# smartmeterif.net
KiCad netlist of a schematic drawn in EAGLE
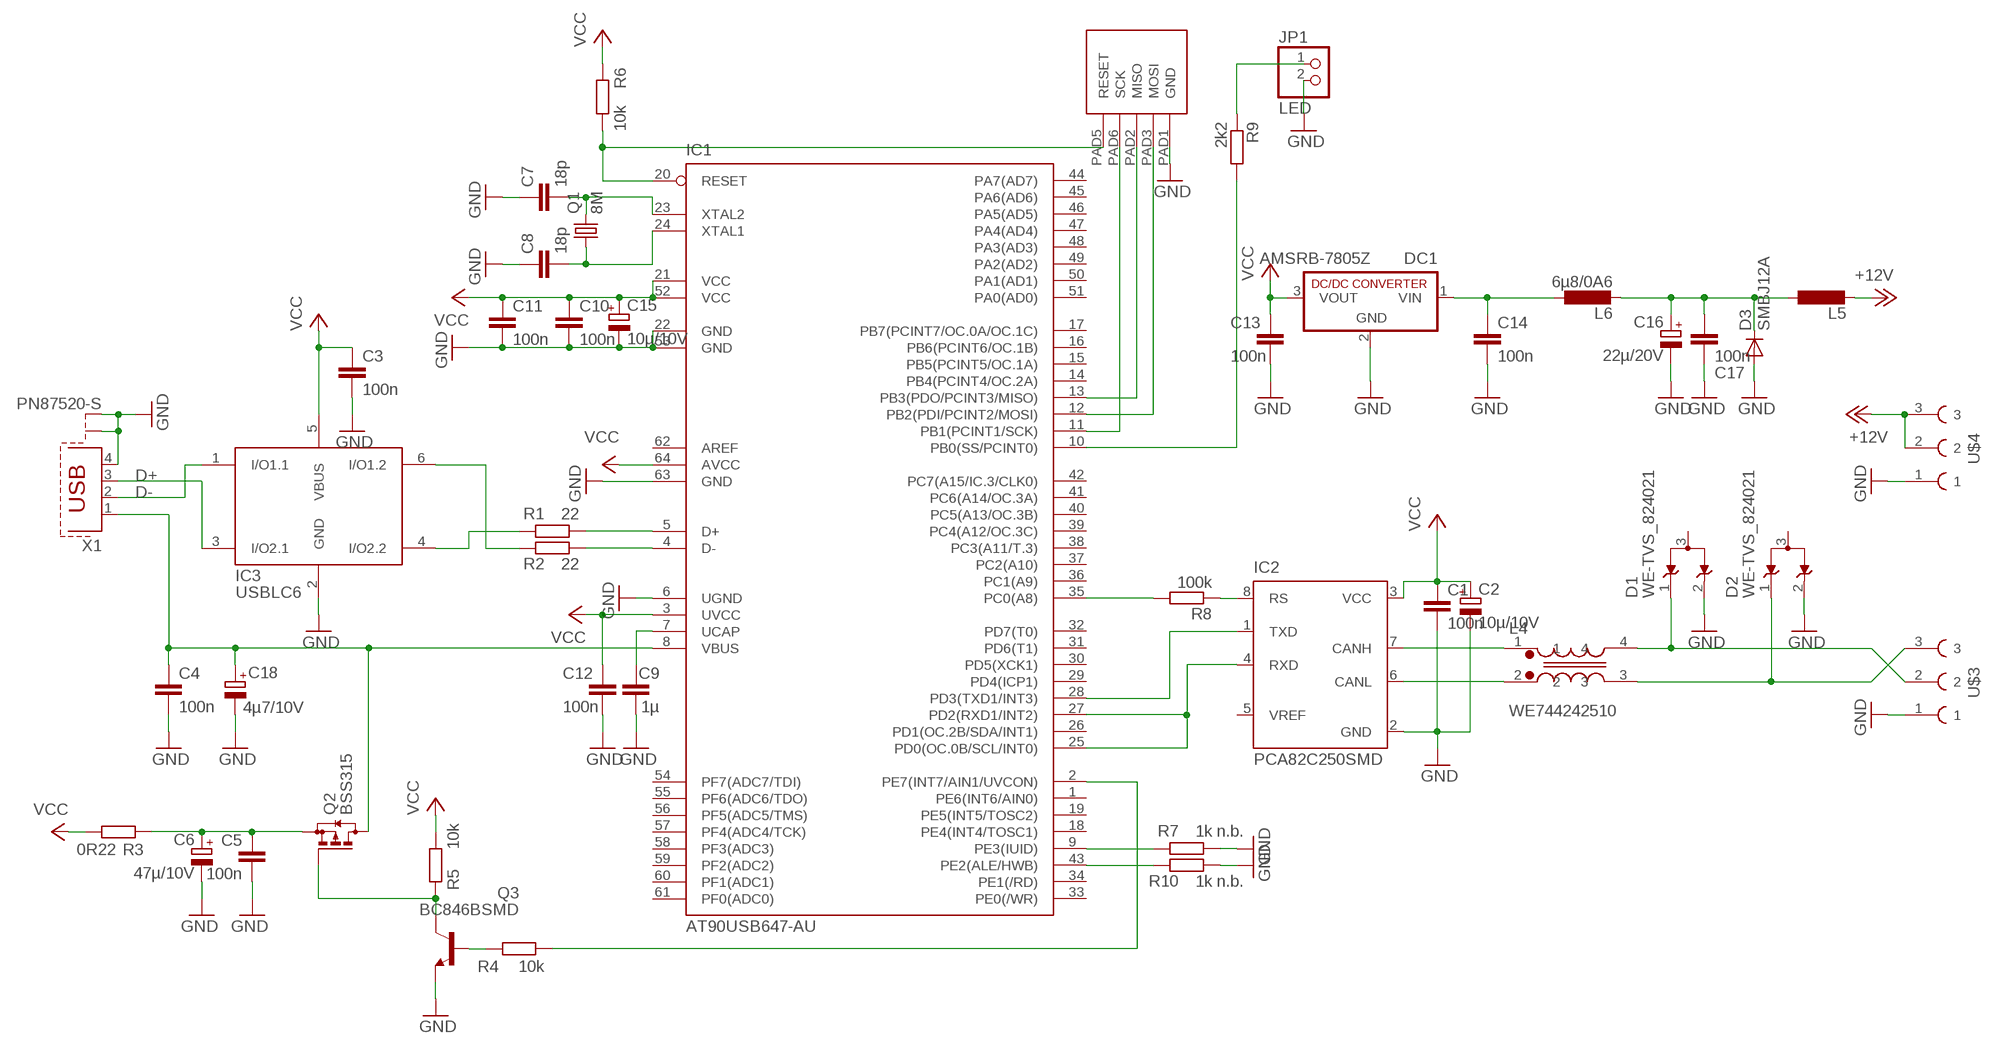
[diagram p0: schematic, sheet 1]

(export (version "E")
  (design (tool "Eeschema 10.0.6"))
  (components
    (comp (ref "C1")
      (value "100n")
      (footprint "eagle-import:C0603")
      (libsource (lib "eagle-import") (part "resistor_C-EUC0603"))
    )
    (comp (ref "C2")
      (value "10µ/10V")
      (footprint "eagle-import:A_3216-18W")
      (libsource (lib "eagle-import") (part "CPOL-EUA/3216-18W"))
    )
    (comp (ref "C3")
      (value "100n")
      (footprint "eagle-import:C0603")
      (libsource (lib "eagle-import") (part "resistor_C-EUC0603"))
    )
    (comp (ref "C4")
      (value "100n")
      (footprint "eagle-import:C0603")
      (libsource (lib "eagle-import") (part "resistor_C-EUC0603"))
    )
    (comp (ref "C5")
      (value "100n")
      (footprint "eagle-import:C0603")
      (libsource (lib "eagle-import") (part "resistor_C-EUC0603"))
    )
    (comp (ref "C6")
      (value "47µ/10V")
      (footprint "eagle-import:SMC_C")
      (libsource (lib "eagle-import") (part "CPOL-EUSMCC"))
    )
    (comp (ref "C7")
      (value "18p")
      (footprint "eagle-import:C0603")
      (libsource (lib "eagle-import") (part "C-EUC0603"))
    )
    (comp (ref "C8")
      (value "18p")
      (footprint "eagle-import:C0603")
      (libsource (lib "eagle-import") (part "C-EUC0603"))
    )
    (comp (ref "C9")
      (value "1µ")
      (footprint "eagle-import:C1210K")
      (libsource (lib "eagle-import") (part "C-EUC1210K"))
    )
    (comp (ref "C10")
      (value "100n")
      (footprint "eagle-import:C0603")
      (libsource (lib "eagle-import") (part "resistor_C-EUC0603"))
    )
    (comp (ref "C11")
      (value "100n")
      (footprint "eagle-import:C0603")
      (libsource (lib "eagle-import") (part "resistor_C-EUC0603"))
    )
    (comp (ref "C12")
      (value "100n")
      (footprint "eagle-import:C0603")
      (libsource (lib "eagle-import") (part "resistor_C-EUC0603"))
    )
    (comp (ref "C13")
      (value "100n")
      (footprint "eagle-import:C0603")
      (libsource (lib "eagle-import") (part "resistor_C-EUC0603"))
    )
    (comp (ref "C14")
      (value "100n")
      (footprint "eagle-import:C0603")
      (libsource (lib "eagle-import") (part "resistor_C-EUC0603"))
    )
    (comp (ref "C15")
      (value "10µ/10V")
      (footprint "eagle-import:A_3216-18W")
      (libsource (lib "eagle-import") (part "CPOL-EUA/3216-18W"))
    )
    (comp (ref "C16")
      (value "22µ/20V")
      (footprint "eagle-import:SMC_C")
      (libsource (lib "eagle-import") (part "CPOL-EUSMCC"))
    )
    (comp (ref "C17")
      (value "100n")
      (footprint "eagle-import:C0603")
      (libsource (lib "eagle-import") (part "resistor_C-EUC0603"))
    )
    (comp (ref "C18")
      (value "4µ7/10V")
      (footprint "eagle-import:SMC_A")
      (libsource (lib "eagle-import") (part "CPOL-EUSMCA"))
    )
    (comp (ref "D1")
      (value "WE-TVS_824021")
      (footprint "eagle-import:WE-TVS_SOT23-3L")
      (libsource (lib "eagle-import") (part "WE-TVS_824021"))
    )
    (comp (ref "D2")
      (value "WE-TVS_824021")
      (footprint "eagle-import:WE-TVS_SOT23-3L")
      (libsource (lib "eagle-import") (part "WE-TVS_824021"))
    )
    (comp (ref "D3")
      (value "SMBJ12A")
      (footprint "eagle-import:SMB")
      (libsource (lib "eagle-import") (part "DIODE-SMB"))
    )
    (comp (ref "DC1")
      (value "AMSRB-7805Z")
      (footprint "eagle-import:SIP3")
      (libsource (lib "eagle-import") (part "R-78C-1.05.0"))
    )
    (comp (ref "IC1")
      (value "AT90USB647-AU")
      (footprint "eagle-import:TQFP64")
      (libsource (lib "eagle-import") (part "AT90USB647-AU"))
    )
    (comp (ref "IC2")
      (value "PCA82C250SMD")
      (footprint "eagle-import:SO8")
      (libsource (lib "eagle-import") (part "PCA82C250SMD"))
    )
    (comp (ref "IC3")
      (value "USBLC6")
      (footprint "eagle-import:SOT23-6L")
      (libsource (lib "eagle-import") (part "USBLC6"))
    )
    (comp (ref "JP1")
      (value "LED")
      (footprint "eagle-import:1X02")
      (libsource (lib "eagle-import") (part "PINHD-1X2"))
    )
    (comp (ref "L4")
      (value "WE744242510")
      (footprint "eagle-import:WE-SLM")
      (libsource (lib "eagle-import") (part "WE-SLM"))
    )
    (comp (ref "L5")
      (value "L-EUL1806")
      (footprint "eagle-import:L1806")
      (libsource (lib "eagle-import") (part "L-EUL1806"))
    )
    (comp (ref "L6")
      (value "6µ8/0A6")
      (footprint "eagle-import:L1812")
      (libsource (lib "eagle-import") (part "rcl_L-EUL1812"))
    )
    (comp (ref "Q1")
      (value "8M")
      (footprint "eagle-import:SM49")
      (libsource (lib "eagle-import") (part "CRYSTALSM49"))
    )
    (comp (ref "Q2")
      (value "BSS315")
      (footprint "eagle-import:SOT23")
      (libsource (lib "eagle-import") (part "BSS84"))
    )
    (comp (ref "Q3")
      (value "BC846BSMD")
      (footprint "eagle-import:SOT23")
      (libsource (lib "eagle-import") (part "BC846SMDB"))
    )
    (comp (ref "R1")
      (value "22")
      (footprint "eagle-import:R0603")
      (libsource (lib "eagle-import") (part "R-EU_R0603"))
    )
    (comp (ref "R2")
      (value "22")
      (footprint "eagle-import:R0603")
      (libsource (lib "eagle-import") (part "R-EU_R0603"))
    )
    (comp (ref "R3")
      (value "0R22")
      (footprint "eagle-import:R0603")
      (libsource (lib "eagle-import") (part "R-EU_R0603"))
    )
    (comp (ref "R4")
      (value "10k")
      (footprint "eagle-import:R0603")
      (libsource (lib "eagle-import") (part "R-EU_R0603"))
    )
    (comp (ref "R5")
      (value "10k")
      (footprint "eagle-import:R0603")
      (libsource (lib "eagle-import") (part "R-EU_R0603"))
    )
    (comp (ref "R6")
      (value "10k")
      (footprint "eagle-import:R0603")
      (libsource (lib "eagle-import") (part "R-EU_R0603"))
    )
    (comp (ref "R7")
      (value "1k n.b.")
      (footprint "eagle-import:R0603")
      (libsource (lib "eagle-import") (part "R-EU_R0603"))
    )
    (comp (ref "R8")
      (value "100k")
      (footprint "eagle-import:R0603")
      (libsource (lib "eagle-import") (part "resistor_R-EU_R0603"))
    )
    (comp (ref "R9")
      (value "2k2")
      (footprint "eagle-import:R0603")
      (libsource (lib "eagle-import") (part "resistor_R-EU_R0603"))
    )
    (comp (ref "R10")
      (value "1k n.b.")
      (footprint "eagle-import:R0603")
      (libsource (lib "eagle-import") (part "R-EU_R0603"))
    )
    (comp (ref "U$2")
      (value "ATMEL_ISP")
      (footprint "eagle-import:ATMEL_ISP")
      (libsource (lib "eagle-import") (part "ATMEL_ISP"))
    )
    (comp (ref "U$3")
      (value "MKDSO_2.5/3_L")
      (footprint "eagle-import:PHOENIX_MKDSO_2.5_3_L")
      (libsource (lib "eagle-import") (part "MKDSO_2.5/3_L"))
    )
    (comp (ref "U$4")
      (value "MKDSO_2.5/3_L")
      (footprint "eagle-import:PHOENIX_MKDSO_2.5_3_L")
      (libsource (lib "eagle-import") (part "MKDSO_2.5/3_L"))
    )
    (comp (ref "X1")
      (value "PN87520-S")
      (footprint "eagle-import:PN87520-S")
      (libsource (lib "eagle-import") (part "PN87520-S"))
    )
  )
  (nets
    (net (code "1") (name "+12V") (class "Default")
      (node (ref "L5") (pin "2") (pinfunction "2_2") (pintype "passive"))
      (node (ref "U$4") (pin "2") (pinfunction "2_2") (pintype "bidirectional"))
      (node (ref "U$4") (pin "3") (pinfunction "3_3") (pintype "bidirectional"))
    )
    (net (code "2") (name "/D+") (class "Default")
      (node (ref "IC3") (pin "3") (pinfunction "I/O2.1_3") (pintype "bidirectional"))
      (node (ref "X1") (pin "3") (pinfunction "3_3") (pintype "passive"))
    )
    (net (code "3") (name "/D-") (class "Default")
      (node (ref "IC3") (pin "1") (pinfunction "I/O1.1_1") (pintype "bidirectional"))
      (node (ref "X1") (pin "2") (pinfunction "2_2") (pintype "passive"))
    )
    (net (code "4") (name "GND") (class "Default")
      (node (ref "C1") (pin "2") (pinfunction "2_2") (pintype "passive"))
      (node (ref "C10") (pin "2") (pinfunction "2_2") (pintype "passive"))
      (node (ref "C11") (pin "2") (pinfunction "2_2") (pintype "passive"))
      (node (ref "C12") (pin "2") (pinfunction "2_2") (pintype "passive"))
      (node (ref "C13") (pin "2") (pinfunction "2_2") (pintype "passive"))
      (node (ref "C14") (pin "2") (pinfunction "2_2") (pintype "passive"))
      (node (ref "C15") (pin "-") (pinfunction "-_-") (pintype "passive"))
      (node (ref "C16") (pin "-") (pinfunction "-_-") (pintype "passive"))
      (node (ref "C17") (pin "2") (pinfunction "2_2") (pintype "passive"))
      (node (ref "C18") (pin "-") (pinfunction "-_-") (pintype "passive"))
      (node (ref "C2") (pin "-") (pinfunction "-_-") (pintype "passive"))
      (node (ref "C3") (pin "2") (pinfunction "2_2") (pintype "passive"))
      (node (ref "C4") (pin "2") (pinfunction "2_2") (pintype "passive"))
      (node (ref "C5") (pin "2") (pinfunction "2_2") (pintype "passive"))
      (node (ref "C6") (pin "-") (pinfunction "-_-") (pintype "passive"))
      (node (ref "C7") (pin "1") (pinfunction "1_1") (pintype "passive"))
      (node (ref "C8") (pin "1") (pinfunction "1_1") (pintype "passive"))
      (node (ref "C9") (pin "1") (pinfunction "1_1") (pintype "passive"))
      (node (ref "D1") (pin "2") (pinfunction "2_2") (pintype "passive"))
      (node (ref "D2") (pin "2") (pinfunction "2_2") (pintype "passive"))
      (node (ref "D3") (pin "A") (pinfunction "A_A") (pintype "passive"))
      (node (ref "DC1") (pin "2") (pinfunction "GND_2") (pintype "passive"))
      (node (ref "IC1") (pin "22") (pinfunction "GND_22") (pintype "power_in"))
      (node (ref "IC1") (pin "53") (pinfunction "GND_53") (pintype "power_in"))
      (node (ref "IC1") (pin "6") (pinfunction "UGND_6") (pintype "power_in"))
      (node (ref "IC1") (pin "63") (pinfunction "GND_63") (pintype "power_in"))
      (node (ref "IC2") (pin "2") (pinfunction "GND_2") (pintype "power_in"))
      (node (ref "IC3") (pin "2") (pinfunction "GND_2") (pintype "power_in"))
      (node (ref "JP1") (pin "2") (pinfunction "2_2") (pintype "passive"))
      (node (ref "Q3") (pin "2") (pinfunction "E_2") (pintype "passive"))
      (node (ref "R10") (pin "2") (pinfunction "2_2") (pintype "passive"))
      (node (ref "R7") (pin "2") (pinfunction "2_2") (pintype "passive"))
      (node (ref "U$2") (pin "PAD1") (pinfunction "GND_PAD1") (pintype "power_in"))
      (node (ref "U$3") (pin "1") (pinfunction "1_1") (pintype "bidirectional"))
      (node (ref "U$4") (pin "1") (pinfunction "1_1") (pintype "bidirectional"))
      (node (ref "X1") (pin "4") (pinfunction "4_4") (pintype "passive"))
      (node (ref "X1") (pin "S1") (pinfunction "S1_S1") (pintype "passive"))
      (node (ref "X1") (pin "S2") (pinfunction "S2_S2") (pintype "passive"))
    )
    (net (code "5") (name "Net-(C16-Pad+)") (class "Default")
      (node (ref "C16") (pin "+") (pinfunction "+_+") (pintype "passive"))
      (node (ref "C17") (pin "1") (pinfunction "1_1") (pintype "passive"))
      (node (ref "D3") (pin "C") (pinfunction "C_C") (pintype "passive"))
      (node (ref "L5") (pin "1") (pinfunction "1_1") (pintype "passive"))
      (node (ref "L6") (pin "2") (pinfunction "2_2") (pintype "passive"))
    )
    (net (code "6") (name "Net-(D1-Pad1)") (class "Default")
      (node (ref "D1") (pin "1") (pinfunction "1_1") (pintype "passive"))
      (node (ref "L4") (pin "4") (pinfunction "4_4") (pintype "bidirectional"))
      (node (ref "U$3") (pin "2") (pinfunction "2_2") (pintype "bidirectional"))
    )
    (net (code "7") (name "Net-(D2-Pad1)") (class "Default")
      (node (ref "D2") (pin "1") (pinfunction "1_1") (pintype "passive"))
      (node (ref "L4") (pin "3") (pinfunction "3_3") (pintype "bidirectional"))
      (node (ref "U$3") (pin "3") (pinfunction "3_3") (pintype "bidirectional"))
    )
    (net (code "8") (name "Net-(DC1-VIN)") (class "Default")
      (node (ref "C14") (pin "1") (pinfunction "1_1") (pintype "passive"))
      (node (ref "DC1") (pin "1") (pinfunction "VIN_1") (pintype "passive"))
      (node (ref "L6") (pin "1") (pinfunction "1_1") (pintype "passive"))
    )
    (net (code "9") (name "Net-(IC1-D+)") (class "Default")
      (node (ref "IC1") (pin "5") (pinfunction "D+_5") (pintype "bidirectional"))
      (node (ref "R1") (pin "2") (pinfunction "2_2") (pintype "passive"))
    )
    (net (code "10") (name "Net-(IC1-D-)") (class "Default")
      (node (ref "IC1") (pin "4") (pinfunction "D-_4") (pintype "bidirectional"))
      (node (ref "R2") (pin "2") (pinfunction "2_2") (pintype "passive"))
    )
    (net (code "11") (name "Net-(IC1-PB0(SS{slash}PCINT0))") (class "Default")
      (node (ref "IC1") (pin "10") (pinfunction "PB0(SS/PCINT0)_10") (pintype "bidirectional"))
      (node (ref "R9") (pin "2") (pinfunction "2_2") (pintype "passive"))
    )
    (net (code "12") (name "Net-(IC1-PB1(PCINT1{slash}SCK))") (class "Default")
      (node (ref "IC1") (pin "11") (pinfunction "PB1(PCINT1/SCK)_11") (pintype "bidirectional"))
      (node (ref "U$2") (pin "PAD6") (pinfunction "SCK_PAD6") (pintype "bidirectional"))
    )
    (net (code "13") (name "Net-(IC1-PB2(PDI{slash}PCINT2{slash}MOSI))") (class "Default")
      (node (ref "IC1") (pin "12") (pinfunction "PB2(PDI/PCINT2/MOSI)_12") (pintype "bidirectional"))
      (node (ref "U$2") (pin "PAD3") (pinfunction "MOSI_PAD3") (pintype "bidirectional"))
    )
    (net (code "14") (name "Net-(IC1-PB3(PDO{slash}PCINT3{slash}MISO))") (class "Default")
      (node (ref "IC1") (pin "13") (pinfunction "PB3(PDO/PCINT3/MISO)_13") (pintype "bidirectional"))
      (node (ref "U$2") (pin "PAD2") (pinfunction "MISO_PAD2") (pintype "bidirectional"))
    )
    (net (code "15") (name "Net-(IC1-PC0(A8))") (class "Default")
      (node (ref "IC1") (pin "35") (pinfunction "PC0(A8)_35") (pintype "bidirectional"))
      (node (ref "R8") (pin "2") (pinfunction "2_2") (pintype "passive"))
    )
    (net (code "16") (name "Net-(IC1-PD0(OC.0B{slash}SCL{slash}INT0))") (class "Default")
      (node (ref "IC1") (pin "25") (pinfunction "PD0(OC.0B/SCL/INT0)_25") (pintype "bidirectional"))
      (node (ref "IC1") (pin "27") (pinfunction "PD2(RXD1/INT2)_27") (pintype "bidirectional"))
      (node (ref "IC2") (pin "4") (pinfunction "RXD_4") (pintype "output"))
    )
    (net (code "17") (name "Net-(IC1-PD3(TXD1{slash}INT3))") (class "Default")
      (node (ref "IC1") (pin "28") (pinfunction "PD3(TXD1/INT3)_28") (pintype "bidirectional"))
      (node (ref "IC2") (pin "1") (pinfunction "TXD_1") (pintype "input"))
    )
    (net (code "18") (name "Net-(IC1-PE2(ALE{slash}HWB))") (class "Default")
      (node (ref "IC1") (pin "43") (pinfunction "PE2(ALE/HWB)_43") (pintype "bidirectional"))
      (node (ref "R10") (pin "1") (pinfunction "1_1") (pintype "passive"))
    )
    (net (code "19") (name "Net-(IC1-PE3(IUID))") (class "Default")
      (node (ref "IC1") (pin "9") (pinfunction "PE3(IUID)_9") (pintype "bidirectional"))
      (node (ref "R7") (pin "1") (pinfunction "1_1") (pintype "passive"))
    )
    (net (code "20") (name "Net-(IC1-PE7(INT7{slash}AIN1{slash}UVCON))") (class "Default")
      (node (ref "IC1") (pin "2") (pinfunction "PE7(INT7/AIN1/UVCON)_2") (pintype "bidirectional"))
      (node (ref "R4") (pin "2") (pinfunction "2_2") (pintype "passive"))
    )
    (net (code "21") (name "Net-(IC1-RESET)") (class "Default")
      (node (ref "IC1") (pin "20") (pinfunction "RESET_20") (pintype "input"))
      (node (ref "R6") (pin "2") (pinfunction "2_2") (pintype "passive"))
      (node (ref "U$2") (pin "PAD5") (pinfunction "RESET_PAD5") (pintype "bidirectional"))
    )
    (net (code "22") (name "Net-(IC1-UCAP)") (class "Default")
      (node (ref "C9") (pin "2") (pinfunction "2_2") (pintype "passive"))
      (node (ref "IC1") (pin "7") (pinfunction "UCAP_7") (pintype "power_in"))
    )
    (net (code "23") (name "Net-(IC1-VBUS)") (class "Default")
      (node (ref "C18") (pin "+") (pinfunction "+_+") (pintype "passive"))
      (node (ref "C4") (pin "1") (pinfunction "1_1") (pintype "passive"))
      (node (ref "IC1") (pin "8") (pinfunction "VBUS_8") (pintype "power_in"))
      (node (ref "Q2") (pin "3") (pinfunction "D_3") (pintype "passive"))
      (node (ref "X1") (pin "1") (pinfunction "1_1") (pintype "passive"))
    )
    (net (code "24") (name "Net-(IC1-XTAL1)") (class "Default")
      (node (ref "C8") (pin "2") (pinfunction "2_2") (pintype "passive"))
      (node (ref "IC1") (pin "24") (pinfunction "XTAL1_24") (pintype "bidirectional"))
      (node (ref "Q1") (pin "1") (pinfunction "1_1") (pintype "passive"))
    )
    (net (code "25") (name "Net-(IC1-XTAL2)") (class "Default")
      (node (ref "C7") (pin "2") (pinfunction "2_2") (pintype "passive"))
      (node (ref "IC1") (pin "23") (pinfunction "XTAL2_23") (pintype "bidirectional"))
      (node (ref "Q1") (pin "2") (pinfunction "2_2") (pintype "passive"))
    )
    (net (code "26") (name "Net-(IC2-CANH)") (class "Default")
      (node (ref "IC2") (pin "7") (pinfunction "CANH_7") (pintype "bidirectional"))
      (node (ref "L4") (pin "1") (pinfunction "1_1") (pintype "bidirectional"))
    )
    (net (code "27") (name "Net-(IC2-CANL)") (class "Default")
      (node (ref "IC2") (pin "6") (pinfunction "CANL_6") (pintype "bidirectional"))
      (node (ref "L4") (pin "2") (pinfunction "2_2") (pintype "bidirectional"))
    )
    (net (code "28") (name "Net-(IC2-RS)") (class "Default")
      (node (ref "IC2") (pin "8") (pinfunction "RS_8") (pintype "input"))
      (node (ref "R8") (pin "1") (pinfunction "1_1") (pintype "passive"))
    )
    (net (code "29") (name "Net-(IC3-I{slash}O1.2)") (class "Default")
      (node (ref "IC3") (pin "6") (pinfunction "I/O1.2_6") (pintype "bidirectional"))
      (node (ref "R2") (pin "1") (pinfunction "1_1") (pintype "passive"))
    )
    (net (code "30") (name "Net-(IC3-I{slash}O2.2)") (class "Default")
      (node (ref "IC3") (pin "4") (pinfunction "I/O2.2_4") (pintype "bidirectional"))
      (node (ref "R1") (pin "1") (pinfunction "1_1") (pintype "passive"))
    )
    (net (code "31") (name "Net-(JP1-Pad1)") (class "Default")
      (node (ref "JP1") (pin "1") (pinfunction "1_1") (pintype "passive"))
      (node (ref "R9") (pin "1") (pinfunction "1_1") (pintype "passive"))
    )
    (net (code "32") (name "Net-(Q2-G)") (class "Default")
      (node (ref "Q2") (pin "1") (pinfunction "G_1") (pintype "passive"))
      (node (ref "Q3") (pin "3") (pinfunction "C_3") (pintype "passive"))
      (node (ref "R5") (pin "1") (pinfunction "1_1") (pintype "passive"))
    )
    (net (code "33") (name "Net-(Q2-S)") (class "Default")
      (node (ref "C5") (pin "1") (pinfunction "1_1") (pintype "passive"))
      (node (ref "C6") (pin "+") (pinfunction "+_+") (pintype "passive"))
      (node (ref "Q2") (pin "2") (pinfunction "S_2") (pintype "passive"))
      (node (ref "R3") (pin "1") (pinfunction "1_1") (pintype "passive"))
    )
    (net (code "34") (name "Net-(Q3-B)") (class "Default")
      (node (ref "Q3") (pin "1") (pinfunction "B_1") (pintype "passive"))
      (node (ref "R4") (pin "1") (pinfunction "1_1") (pintype "passive"))
    )
    (net (code "35") (name "VCC") (class "Default")
      (node (ref "C1") (pin "1") (pinfunction "1_1") (pintype "passive"))
      (node (ref "C10") (pin "1") (pinfunction "1_1") (pintype "passive"))
      (node (ref "C11") (pin "1") (pinfunction "1_1") (pintype "passive"))
      (node (ref "C12") (pin "1") (pinfunction "1_1") (pintype "passive"))
      (node (ref "C13") (pin "1") (pinfunction "1_1") (pintype "passive"))
      (node (ref "C15") (pin "+") (pinfunction "+_+") (pintype "passive"))
      (node (ref "C2") (pin "+") (pinfunction "+_+") (pintype "passive"))
      (node (ref "C3") (pin "1") (pinfunction "1_1") (pintype "passive"))
      (node (ref "DC1") (pin "3") (pinfunction "VOUT_3") (pintype "passive"))
      (node (ref "IC1") (pin "21") (pinfunction "VCC_21") (pintype "power_in"))
      (node (ref "IC1") (pin "3") (pinfunction "UVCC_3") (pintype "power_in"))
      (node (ref "IC1") (pin "52") (pinfunction "VCC_52") (pintype "power_in"))
      (node (ref "IC1") (pin "64") (pinfunction "AVCC_64") (pintype "bidirectional"))
      (node (ref "IC2") (pin "3") (pinfunction "VCC_3") (pintype "power_in"))
      (node (ref "IC3") (pin "5") (pinfunction "VBUS_5") (pintype "power_in"))
      (node (ref "R3") (pin "2") (pinfunction "2_2") (pintype "passive"))
      (node (ref "R5") (pin "2") (pinfunction "2_2") (pintype "passive"))
      (node (ref "R6") (pin "1") (pinfunction "1_1") (pintype "passive"))
    )
    (net (code "36") (name "unconnected-(D1-GND-Pad3)") (class "Default")
      (node (ref "D1") (pin "3") (pinfunction "GND_3") (pintype "passive"))
    )
    (net (code "37") (name "unconnected-(D2-GND-Pad3)") (class "Default")
      (node (ref "D2") (pin "3") (pinfunction "GND_3") (pintype "passive"))
    )
    (net (code "38") (name "unconnected-(IC1-AREF-Pad62)") (class "Default")
      (node (ref "IC1") (pin "62") (pinfunction "AREF_62") (pintype "bidirectional"))
    )
    (net (code "39") (name "unconnected-(IC1-PA0(AD0)-Pad51)") (class "Default")
      (node (ref "IC1") (pin "51") (pinfunction "PA0(AD0)_51") (pintype "bidirectional"))
    )
    (net (code "40") (name "unconnected-(IC1-PA1(AD1)-Pad50)") (class "Default")
      (node (ref "IC1") (pin "50") (pinfunction "PA1(AD1)_50") (pintype "bidirectional"))
    )
    (net (code "41") (name "unconnected-(IC1-PA2(AD2)-Pad49)") (class "Default")
      (node (ref "IC1") (pin "49") (pinfunction "PA2(AD2)_49") (pintype "bidirectional"))
    )
    (net (code "42") (name "unconnected-(IC1-PA3(AD3)-Pad48)") (class "Default")
      (node (ref "IC1") (pin "48") (pinfunction "PA3(AD3)_48") (pintype "bidirectional"))
    )
    (net (code "43") (name "unconnected-(IC1-PA4(AD4)-Pad47)") (class "Default")
      (node (ref "IC1") (pin "47") (pinfunction "PA4(AD4)_47") (pintype "bidirectional"))
    )
    (net (code "44") (name "unconnected-(IC1-PA5(AD5)-Pad46)") (class "Default")
      (node (ref "IC1") (pin "46") (pinfunction "PA5(AD5)_46") (pintype "bidirectional"))
    )
    (net (code "45") (name "unconnected-(IC1-PA6(AD6)-Pad45)") (class "Default")
      (node (ref "IC1") (pin "45") (pinfunction "PA6(AD6)_45") (pintype "bidirectional"))
    )
    (net (code "46") (name "unconnected-(IC1-PA7(AD7)-Pad44)") (class "Default")
      (node (ref "IC1") (pin "44") (pinfunction "PA7(AD7)_44") (pintype "bidirectional"))
    )
    (net (code "47") (name "unconnected-(IC1-PB4(PCINT4{slash}OC.2A)-Pad14)") (class "Default")
      (node (ref "IC1") (pin "14") (pinfunction "PB4(PCINT4/OC.2A)_14") (pintype "bidirectional"))
    )
    (net (code "48") (name "unconnected-(IC1-PB5(PCINT5{slash}OC.1A)-Pad15)") (class "Default")
      (node (ref "IC1") (pin "15") (pinfunction "PB5(PCINT5/OC.1A)_15") (pintype "bidirectional"))
    )
    (net (code "49") (name "unconnected-(IC1-PB6(PCINT6{slash}OC.1B)-Pad16)") (class "Default")
      (node (ref "IC1") (pin "16") (pinfunction "PB6(PCINT6/OC.1B)_16") (pintype "bidirectional"))
    )
    (net (code "50") (name "unconnected-(IC1-PB7(PCINT7{slash}OC.0A{slash}OC.1C)-Pad17)") (class "Default")
      (node (ref "IC1") (pin "17") (pinfunction "PB7(PCINT7/OC.0A/OC.1C)_17") (pintype "bidirectional"))
    )
    (net (code "51") (name "unconnected-(IC1-PC1(A9)-Pad36)") (class "Default")
      (node (ref "IC1") (pin "36") (pinfunction "PC1(A9)_36") (pintype "bidirectional"))
    )
    (net (code "52") (name "unconnected-(IC1-PC2(A10)-Pad37)") (class "Default")
      (node (ref "IC1") (pin "37") (pinfunction "PC2(A10)_37") (pintype "bidirectional"))
    )
    (net (code "53") (name "unconnected-(IC1-PC3(A11{slash}T.3)-Pad38)") (class "Default")
      (node (ref "IC1") (pin "38") (pinfunction "PC3(A11/T.3)_38") (pintype "bidirectional"))
    )
    (net (code "54") (name "unconnected-(IC1-PC4(A12{slash}OC.3C)-Pad39)") (class "Default")
      (node (ref "IC1") (pin "39") (pinfunction "PC4(A12/OC.3C)_39") (pintype "bidirectional"))
    )
    (net (code "55") (name "unconnected-(IC1-PC5(A13{slash}OC.3B)-Pad40)") (class "Default")
      (node (ref "IC1") (pin "40") (pinfunction "PC5(A13/OC.3B)_40") (pintype "bidirectional"))
    )
    (net (code "56") (name "unconnected-(IC1-PC6(A14{slash}OC.3A)-Pad41)") (class "Default")
      (node (ref "IC1") (pin "41") (pinfunction "PC6(A14/OC.3A)_41") (pintype "bidirectional"))
    )
    (net (code "57") (name "unconnected-(IC1-PC7(A15{slash}IC.3{slash}CLK0)-Pad42)") (class "Default")
      (node (ref "IC1") (pin "42") (pinfunction "PC7(A15/IC.3/CLK0)_42") (pintype "bidirectional"))
    )
    (net (code "58") (name "unconnected-(IC1-PD1(OC.2B{slash}SDA{slash}INT1)-Pad26)") (class "Default")
      (node (ref "IC1") (pin "26") (pinfunction "PD1(OC.2B/SDA/INT1)_26") (pintype "bidirectional"))
    )
    (net (code "59") (name "unconnected-(IC1-PD4(ICP1)-Pad29)") (class "Default")
      (node (ref "IC1") (pin "29") (pinfunction "PD4(ICP1)_29") (pintype "bidirectional"))
    )
    (net (code "60") (name "unconnected-(IC1-PD5(XCK1)-Pad30)") (class "Default")
      (node (ref "IC1") (pin "30") (pinfunction "PD5(XCK1)_30") (pintype "bidirectional"))
    )
    (net (code "61") (name "unconnected-(IC1-PD6(T1)-Pad31)") (class "Default")
      (node (ref "IC1") (pin "31") (pinfunction "PD6(T1)_31") (pintype "bidirectional"))
    )
    (net (code "62") (name "unconnected-(IC1-PD7(T0)-Pad32)") (class "Default")
      (node (ref "IC1") (pin "32") (pinfunction "PD7(T0)_32") (pintype "bidirectional"))
    )
    (net (code "63") (name "unconnected-(IC1-PE0({slash}WR)-Pad33)") (class "Default")
      (node (ref "IC1") (pin "33") (pinfunction "PE0(/WR)_33") (pintype "bidirectional"))
    )
    (net (code "64") (name "unconnected-(IC1-PE1({slash}RD)-Pad34)") (class "Default")
      (node (ref "IC1") (pin "34") (pinfunction "PE1(/RD)_34") (pintype "bidirectional"))
    )
    (net (code "65") (name "unconnected-(IC1-PE4(INT4{slash}TOSC1)-Pad18)") (class "Default")
      (node (ref "IC1") (pin "18") (pinfunction "PE4(INT4/TOSC1)_18") (pintype "bidirectional"))
    )
    (net (code "66") (name "unconnected-(IC1-PE5(INT5{slash}TOSC2)-Pad19)") (class "Default")
      (node (ref "IC1") (pin "19") (pinfunction "PE5(INT5/TOSC2)_19") (pintype "bidirectional"))
    )
    (net (code "67") (name "unconnected-(IC1-PE6(INT6{slash}AIN0)-Pad1)") (class "Default")
      (node (ref "IC1") (pin "1") (pinfunction "PE6(INT6/AIN0)_1") (pintype "bidirectional"))
    )
    (net (code "68") (name "unconnected-(IC1-PF0(ADC0)-Pad61)") (class "Default")
      (node (ref "IC1") (pin "61") (pinfunction "PF0(ADC0)_61") (pintype "bidirectional"))
    )
    (net (code "69") (name "unconnected-(IC1-PF1(ADC1)-Pad60)") (class "Default")
      (node (ref "IC1") (pin "60") (pinfunction "PF1(ADC1)_60") (pintype "bidirectional"))
    )
    (net (code "70") (name "unconnected-(IC1-PF2(ADC2)-Pad59)") (class "Default")
      (node (ref "IC1") (pin "59") (pinfunction "PF2(ADC2)_59") (pintype "bidirectional"))
    )
    (net (code "71") (name "unconnected-(IC1-PF3(ADC3)-Pad58)") (class "Default")
      (node (ref "IC1") (pin "58") (pinfunction "PF3(ADC3)_58") (pintype "bidirectional"))
    )
    (net (code "72") (name "unconnected-(IC1-PF4(ADC4{slash}TCK)-Pad57)") (class "Default")
      (node (ref "IC1") (pin "57") (pinfunction "PF4(ADC4/TCK)_57") (pintype "bidirectional"))
    )
    (net (code "73") (name "unconnected-(IC1-PF5(ADC5{slash}TMS)-Pad56)") (class "Default")
      (node (ref "IC1") (pin "56") (pinfunction "PF5(ADC5/TMS)_56") (pintype "bidirectional"))
    )
    (net (code "74") (name "unconnected-(IC1-PF6(ADC6{slash}TDO)-Pad55)") (class "Default")
      (node (ref "IC1") (pin "55") (pinfunction "PF6(ADC6/TDO)_55") (pintype "bidirectional"))
    )
    (net (code "75") (name "unconnected-(IC1-PF7(ADC7{slash}TDI)-Pad54)") (class "Default")
      (node (ref "IC1") (pin "54") (pinfunction "PF7(ADC7/TDI)_54") (pintype "bidirectional"))
    )
    (net (code "76") (name "unconnected-(IC2-VREF-Pad5)") (class "Default")
      (node (ref "IC2") (pin "5") (pinfunction "VREF_5") (pintype "output"))
    )
  )
)
